# Nucleo.net
KiCad netlist of a schematic drawn in Altium Designer
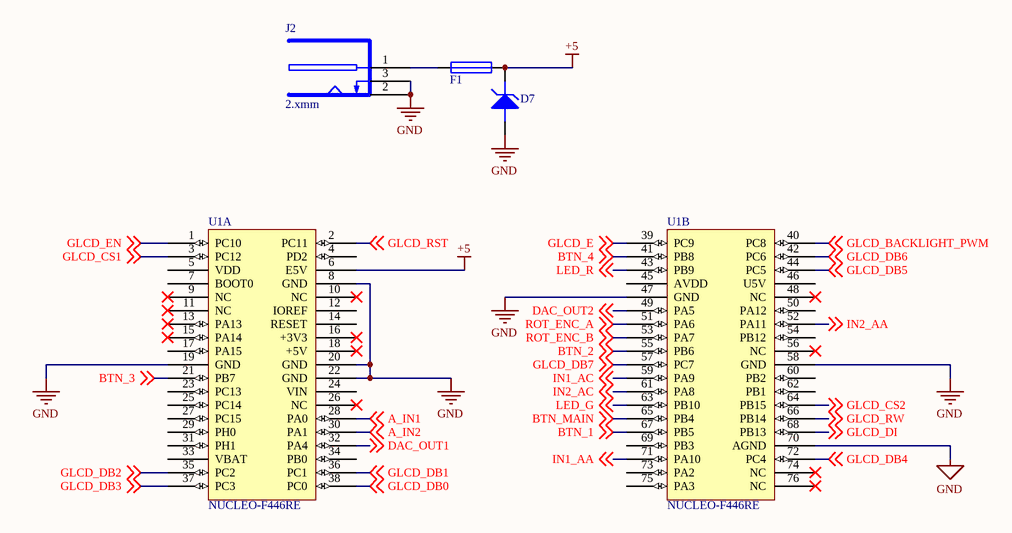
[diagram p0: Nucleo.SchDoc]

(export (version "E")
  (design (tool "Eeschema 10.0.6"))
  (components
    (comp (ref "D7")
      (value "TRANS SUPPR")
      (footprint "FP_SMB")
      (description "Transient suppressor")
      (fields (field (name "VOLTAGE") "6.7V"))
      (libsource (lib "hallglib") (part "TRANS SUPPR"))
    )
    (comp (ref "F1")
      (value "Multifuse")
      (footprint "FP_MULTIFUSE")
      (description "1812 Multifuse")
      (libsource (lib "hallglib") (part "Multifuse"))
    )
    (comp (ref "J2")
      (value "2.xmm")
      (footprint "FP_DC_TAP_ANYA")
      (description "2.xmm DC HEBA25 TÁPFESZÜLTSÉG ALJZAT ZÁRT, NYÁKBA 90°")
      (libsource (lib "hallglib") (part "DC_TAP_ANYA"))
    )
    (comp (ref "U1")
      (value "NUCLEO-F446RE")
      (footprint "FP_NUCLEO-64")
      (libsource (lib "hallglib") (part "NUCLEO-F446RE"))
    )
  )
  (nets
    (net (code "1") (name "+5") (class "Default")
      (node (ref "D7") (pin "1") (pinfunction "CATHODE_1") (pintype "passive"))
      (node (ref "F1") (pin "2") (pinfunction "2_2") (pintype "passive"))
      (node (ref "U1") (pin "6") (pinfunction "E5V_6") (pintype "power_in"))
    )
    (net (code "2") (name "A_IN1") (class "Default")
      (node (ref "U1") (pin "28") (pinfunction "PA0_28") (pintype "bidirectional"))
    )
    (net (code "3") (name "A_IN2") (class "Default")
      (node (ref "U1") (pin "30") (pinfunction "PA1_30") (pintype "bidirectional"))
    )
    (net (code "4") (name "BTN_1") (class "Default")
      (node (ref "U1") (pin "67") (pinfunction "PB5_67") (pintype "bidirectional"))
    )
    (net (code "5") (name "BTN_2") (class "Default")
      (node (ref "U1") (pin "55") (pinfunction "PB6_55") (pintype "bidirectional"))
    )
    (net (code "6") (name "BTN_3") (class "Default")
      (node (ref "U1") (pin "21") (pinfunction "PB7_21") (pintype "bidirectional"))
    )
    (net (code "7") (name "BTN_4") (class "Default")
      (node (ref "U1") (pin "41") (pinfunction "PB8_41") (pintype "bidirectional"))
    )
    (net (code "8") (name "BTN_MAIN") (class "Default")
      (node (ref "U1") (pin "65") (pinfunction "PB4_65") (pintype "bidirectional"))
    )
    (net (code "9") (name "DAC_OUT1") (class "Default")
      (node (ref "U1") (pin "32") (pinfunction "PA4_32") (pintype "bidirectional"))
    )
    (net (code "10") (name "DAC_OUT2") (class "Default")
      (node (ref "U1") (pin "49") (pinfunction "PA5_49") (pintype "bidirectional"))
    )
    (net (code "11") (name "GLCD_BACKLIGHT_PWM") (class "Default")
      (node (ref "U1") (pin "40") (pinfunction "PC8_40") (pintype "bidirectional"))
    )
    (net (code "12") (name "GLCD_CS1") (class "Default")
      (node (ref "U1") (pin "3") (pinfunction "PC12_3") (pintype "bidirectional"))
    )
    (net (code "13") (name "GLCD_CS2") (class "Default")
      (node (ref "U1") (pin "64") (pinfunction "PB15_64") (pintype "bidirectional"))
    )
    (net (code "14") (name "GLCD_DB0") (class "Default")
      (node (ref "U1") (pin "38") (pinfunction "PC0_38") (pintype "bidirectional"))
    )
    (net (code "15") (name "GLCD_DB1") (class "Default")
      (node (ref "U1") (pin "36") (pinfunction "PC1_36") (pintype "bidirectional"))
    )
    (net (code "16") (name "GLCD_DB2") (class "Default")
      (node (ref "U1") (pin "35") (pinfunction "PC2_35") (pintype "bidirectional"))
    )
    (net (code "17") (name "GLCD_DB3") (class "Default")
      (node (ref "U1") (pin "37") (pinfunction "PC3_37") (pintype "bidirectional"))
    )
    (net (code "18") (name "GLCD_DB4") (class "Default")
      (node (ref "U1") (pin "72") (pinfunction "PC4_72") (pintype "bidirectional"))
    )
    (net (code "19") (name "GLCD_DB5") (class "Default")
      (node (ref "U1") (pin "44") (pinfunction "PC5_44") (pintype "bidirectional"))
    )
    (net (code "20") (name "GLCD_DB6") (class "Default")
      (node (ref "U1") (pin "42") (pinfunction "PC6_42") (pintype "bidirectional"))
    )
    (net (code "21") (name "GLCD_DB7") (class "Default")
      (node (ref "U1") (pin "57") (pinfunction "PC7_57") (pintype "bidirectional"))
    )
    (net (code "22") (name "GLCD_DI") (class "Default")
      (node (ref "U1") (pin "68") (pinfunction "PB13_68") (pintype "bidirectional"))
    )
    (net (code "23") (name "GLCD_E") (class "Default")
      (node (ref "U1") (pin "39") (pinfunction "PC9_39") (pintype "bidirectional"))
    )
    (net (code "24") (name "GLCD_EN") (class "Default")
      (node (ref "U1") (pin "1") (pinfunction "PC10_1") (pintype "bidirectional"))
    )
    (net (code "25") (name "GLCD_RST") (class "Default")
      (node (ref "U1") (pin "2") (pinfunction "PC11_2") (pintype "bidirectional"))
    )
    (net (code "26") (name "GLCD_RW") (class "Default")
      (node (ref "U1") (pin "66") (pinfunction "PB14_66") (pintype "bidirectional"))
    )
    (net (code "27") (name "GND") (class "Default")
      (node (ref "D7") (pin "2") (pinfunction "ANODE_2") (pintype "passive"))
      (node (ref "J2") (pin "2") (pinfunction "SLEEVE_2") (pintype "power_in"))
      (node (ref "J2") (pin "3") (pinfunction "BREAK_3") (pintype "power_in"))
      (node (ref "U1") (pin "19") (pinfunction "GND_19") (pintype "passive"))
      (node (ref "U1") (pin "20") (pinfunction "GND_20") (pintype "passive"))
      (node (ref "U1") (pin "22") (pinfunction "GND_22") (pintype "passive"))
      (node (ref "U1") (pin "47") (pinfunction "GND_47") (pintype "passive"))
      (node (ref "U1") (pin "58") (pinfunction "GND_58") (pintype "passive"))
      (node (ref "U1") (pin "70") (pinfunction "AGND_70") (pintype "passive"))
      (node (ref "U1") (pin "8") (pinfunction "GND_8") (pintype "passive"))
    )
    (net (code "28") (name "IN1_AA") (class "Default")
      (node (ref "U1") (pin "71") (pinfunction "PA10_71") (pintype "bidirectional"))
    )
    (net (code "29") (name "IN1_AC") (class "Default")
      (node (ref "U1") (pin "59") (pinfunction "PA9_59") (pintype "bidirectional"))
    )
    (net (code "30") (name "IN2_AA") (class "Default")
      (node (ref "U1") (pin "52") (pinfunction "PA11_52") (pintype "bidirectional"))
    )
    (net (code "31") (name "IN2_AC") (class "Default")
      (node (ref "U1") (pin "61") (pinfunction "PA8_61") (pintype "bidirectional"))
    )
    (net (code "32") (name "LED_G") (class "Default")
      (node (ref "U1") (pin "63") (pinfunction "PB10_63") (pintype "bidirectional"))
    )
    (net (code "33") (name "LED_R") (class "Default")
      (node (ref "U1") (pin "43") (pinfunction "PB9_43") (pintype "bidirectional"))
    )
    (net (code "34") (name "Net-(J2-PIN)") (class "Default")
      (node (ref "F1") (pin "1") (pinfunction "1_1") (pintype "passive"))
      (node (ref "J2") (pin "1") (pinfunction "PIN_1") (pintype "power_in"))
    )
    (net (code "35") (name "ROT_ENC_A") (class "Default")
      (node (ref "U1") (pin "51") (pinfunction "PA6_51") (pintype "bidirectional"))
    )
    (net (code "36") (name "ROT_ENC_B") (class "Default")
      (node (ref "U1") (pin "53") (pinfunction "PA7_53") (pintype "bidirectional"))
    )
    (net (code "37") (name "unconnected-(U1A-+3V3-Pad16)") (class "Default")
      (node (ref "U1") (pin "16") (pinfunction "+3V3_16") (pintype "power_in+no_connect"))
    )
    (net (code "38") (name "unconnected-(U1A-+5V-Pad18)") (class "Default")
      (node (ref "U1") (pin "18") (pinfunction "+5V_18") (pintype "power_in+no_connect"))
    )
    (net (code "39") (name "unconnected-(U1A-BOOT0-Pad7)") (class "Default")
      (node (ref "U1") (pin "7") (pinfunction "BOOT0_7") (pintype "passive"))
    )
    (net (code "40") (name "unconnected-(U1A-IOREF-Pad12)") (class "Default")
      (node (ref "U1") (pin "12") (pinfunction "IOREF_12") (pintype "passive"))
    )
    (net (code "41") (name "unconnected-(U1A-NC-Pad9)") (class "Default")
      (node (ref "U1") (pin "9") (pinfunction "NC_9") (pintype "passive+no_connect"))
    )
    (net (code "42") (name "unconnected-(U1A-NC-Pad10)") (class "Default")
      (node (ref "U1") (pin "10") (pinfunction "NC_10") (pintype "passive+no_connect"))
    )
    (net (code "43") (name "unconnected-(U1A-NC-Pad11)") (class "Default")
      (node (ref "U1") (pin "11") (pinfunction "NC_11") (pintype "passive+no_connect"))
    )
    (net (code "44") (name "unconnected-(U1A-NC-Pad26)") (class "Default")
      (node (ref "U1") (pin "26") (pinfunction "NC_26") (pintype "passive+no_connect"))
    )
    (net (code "45") (name "unconnected-(U1A-PA13-Pad13)") (class "Default")
      (node (ref "U1") (pin "13") (pinfunction "PA13_13") (pintype "bidirectional+no_connect"))
    )
    (net (code "46") (name "unconnected-(U1A-PA14-Pad15)") (class "Default")
      (node (ref "U1") (pin "15") (pinfunction "PA14_15") (pintype "bidirectional+no_connect"))
    )
    (net (code "47") (name "unconnected-(U1A-PA15-Pad17)") (class "Default")
      (node (ref "U1") (pin "17") (pinfunction "PA15_17") (pintype "bidirectional"))
    )
    (net (code "48") (name "unconnected-(U1A-PB0-Pad34)") (class "Default")
      (node (ref "U1") (pin "34") (pinfunction "PB0_34") (pintype "bidirectional"))
    )
    (net (code "49") (name "unconnected-(U1A-PC13-Pad23)") (class "Default")
      (node (ref "U1") (pin "23") (pinfunction "PC13_23") (pintype "bidirectional"))
    )
    (net (code "50") (name "unconnected-(U1A-PC14-Pad25)") (class "Default")
      (node (ref "U1") (pin "25") (pinfunction "PC14_25") (pintype "bidirectional"))
    )
    (net (code "51") (name "unconnected-(U1A-PC15-Pad27)") (class "Default")
      (node (ref "U1") (pin "27") (pinfunction "PC15_27") (pintype "bidirectional"))
    )
    (net (code "52") (name "unconnected-(U1A-PD2-Pad4)") (class "Default")
      (node (ref "U1") (pin "4") (pinfunction "PD2_4") (pintype "bidirectional"))
    )
    (net (code "53") (name "unconnected-(U1A-PH0-Pad29)") (class "Default")
      (node (ref "U1") (pin "29") (pinfunction "PH0_29") (pintype "bidirectional"))
    )
    (net (code "54") (name "unconnected-(U1A-PH1-Pad31)") (class "Default")
      (node (ref "U1") (pin "31") (pinfunction "PH1_31") (pintype "bidirectional"))
    )
    (net (code "55") (name "unconnected-(U1A-RESET-Pad14)") (class "Default")
      (node (ref "U1") (pin "14") (pinfunction "RESET_14") (pintype "passive"))
    )
    (net (code "56") (name "unconnected-(U1A-VBAT-Pad33)") (class "Default")
      (node (ref "U1") (pin "33") (pinfunction "VBAT_33") (pintype "power_in"))
    )
    (net (code "57") (name "unconnected-(U1A-VDD-Pad5)") (class "Default")
      (node (ref "U1") (pin "5") (pinfunction "VDD_5") (pintype "power_in"))
    )
    (net (code "58") (name "unconnected-(U1A-VIN-Pad24)") (class "Default")
      (node (ref "U1") (pin "24") (pinfunction "VIN_24") (pintype "power_in"))
    )
    (net (code "59") (name "unconnected-(U1B-AVDD-Pad45)") (class "Default")
      (node (ref "U1") (pin "45") (pinfunction "AVDD_45") (pintype "power_in"))
    )
    (net (code "60") (name "unconnected-(U1B-NC-Pad48)") (class "Default")
      (node (ref "U1") (pin "48") (pinfunction "NC_48") (pintype "passive+no_connect"))
    )
    (net (code "61") (name "unconnected-(U1B-NC-Pad56)") (class "Default")
      (node (ref "U1") (pin "56") (pinfunction "NC_56") (pintype "passive+no_connect"))
    )
    (net (code "62") (name "unconnected-(U1B-NC-Pad74)") (class "Default")
      (node (ref "U1") (pin "74") (pinfunction "NC_74") (pintype "passive+no_connect"))
    )
    (net (code "63") (name "unconnected-(U1B-NC-Pad76)") (class "Default")
      (node (ref "U1") (pin "76") (pinfunction "NC_76") (pintype "passive+no_connect"))
    )
    (net (code "64") (name "unconnected-(U1B-PA2-Pad73)") (class "Default")
      (node (ref "U1") (pin "73") (pinfunction "PA2_73") (pintype "bidirectional"))
    )
    (net (code "65") (name "unconnected-(U1B-PA3-Pad75)") (class "Default")
      (node (ref "U1") (pin "75") (pinfunction "PA3_75") (pintype "bidirectional"))
    )
    (net (code "66") (name "unconnected-(U1B-PA12-Pad50)") (class "Default")
      (node (ref "U1") (pin "50") (pinfunction "PA12_50") (pintype "bidirectional"))
    )
    (net (code "67") (name "unconnected-(U1B-PB1-Pad62)") (class "Default")
      (node (ref "U1") (pin "62") (pinfunction "PB1_62") (pintype "bidirectional"))
    )
    (net (code "68") (name "unconnected-(U1B-PB2-Pad60)") (class "Default")
      (node (ref "U1") (pin "60") (pinfunction "PB2_60") (pintype "bidirectional"))
    )
    (net (code "69") (name "unconnected-(U1B-PB3-Pad69)") (class "Default")
      (node (ref "U1") (pin "69") (pinfunction "PB3_69") (pintype "bidirectional"))
    )
    (net (code "70") (name "unconnected-(U1B-PB12-Pad54)") (class "Default")
      (node (ref "U1") (pin "54") (pinfunction "PB12_54") (pintype "bidirectional"))
    )
    (net (code "71") (name "unconnected-(U1B-U5V-Pad46)") (class "Default")
      (node (ref "U1") (pin "46") (pinfunction "U5V_46") (pintype "power_in"))
    )
  )
)
